# ProtoSnap-LilyPad_Development_Board.net
KiCad netlist of a schematic drawn in EAGLE
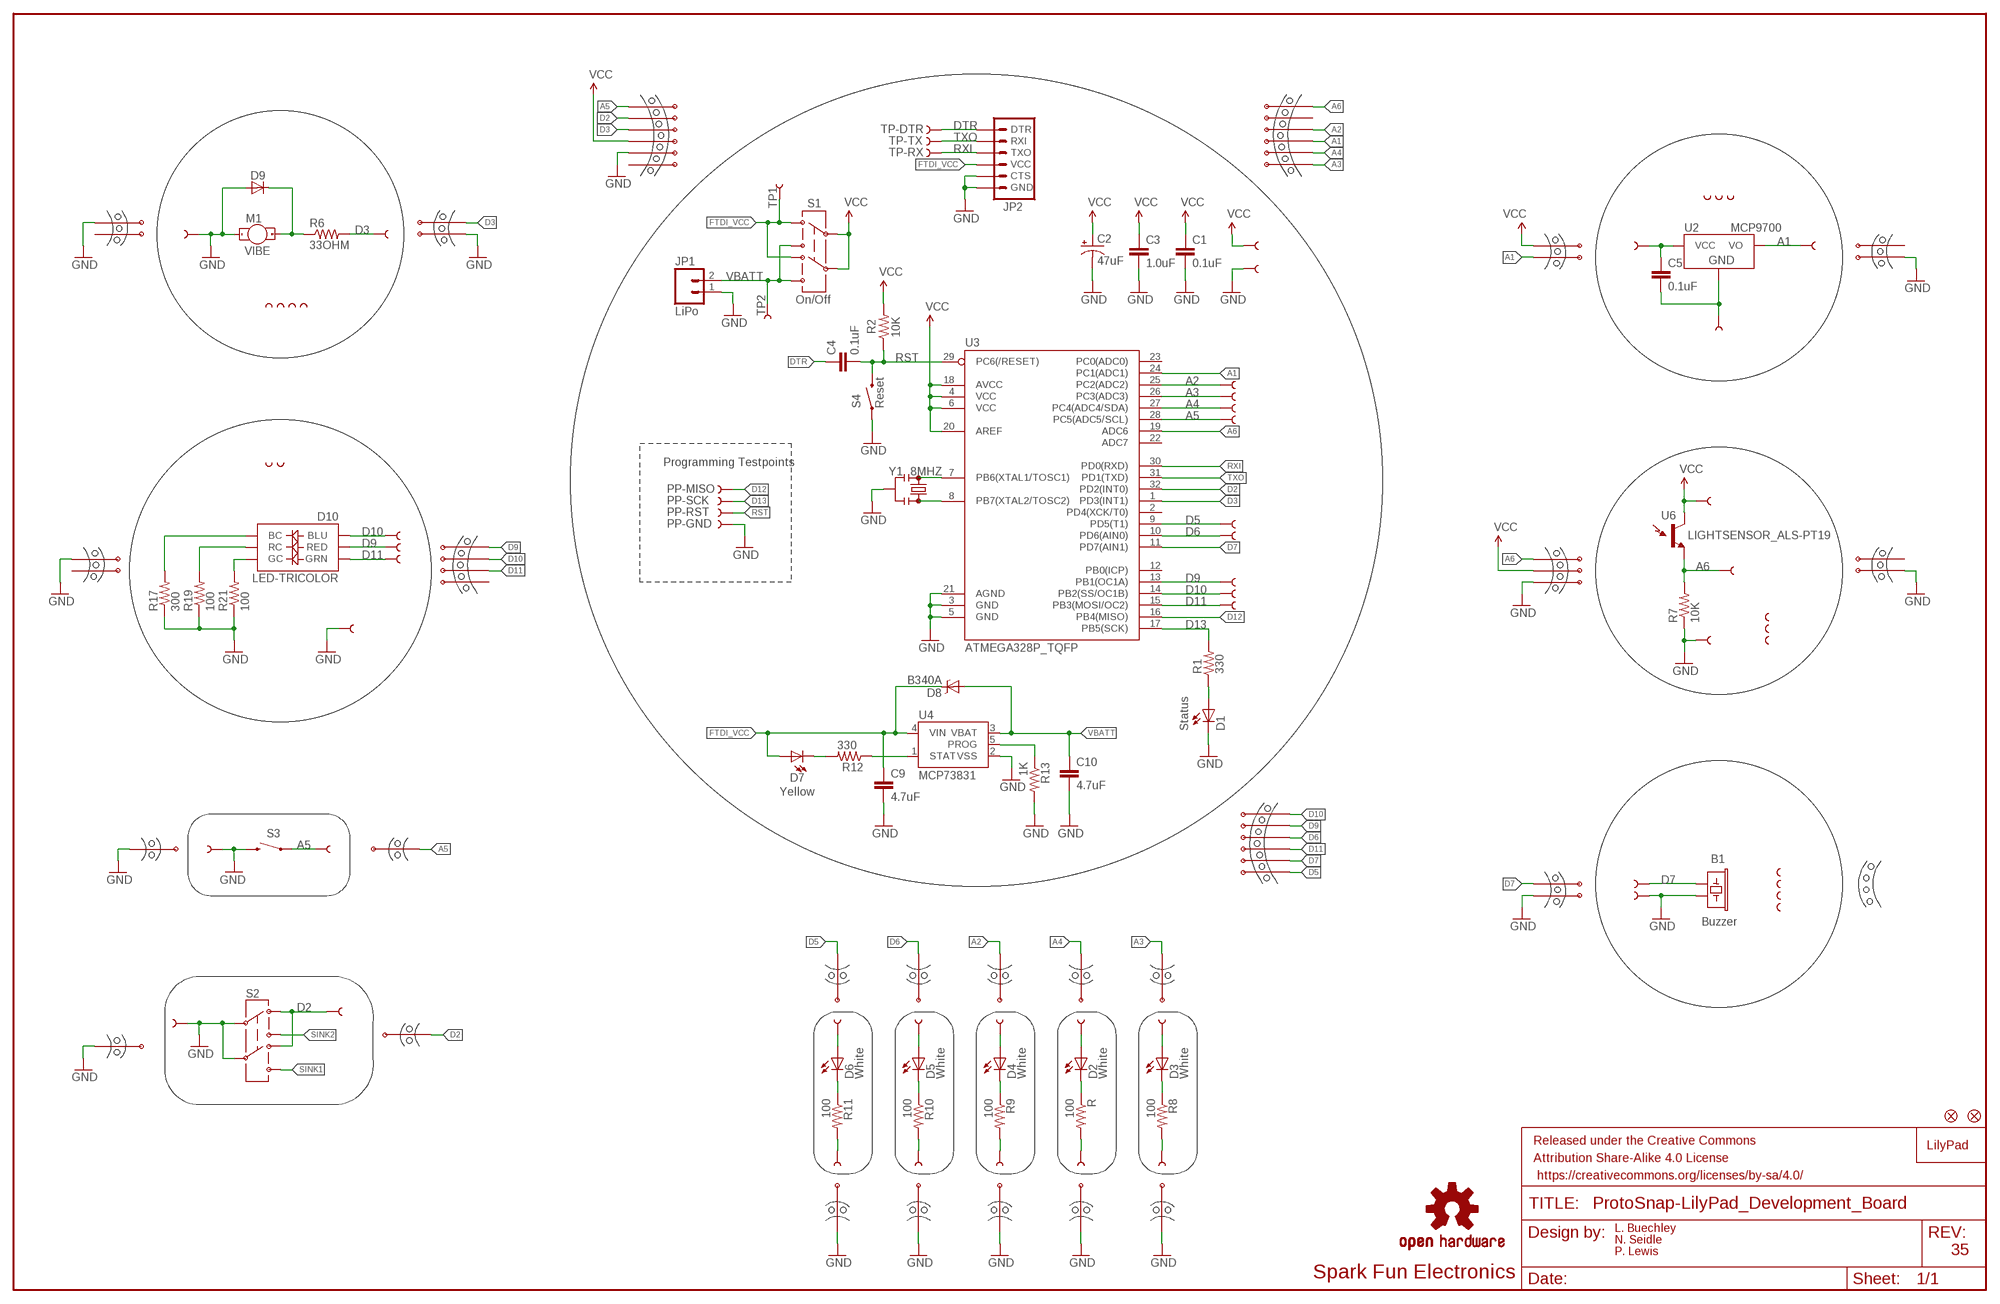
[diagram p0: schematic, sheet 1]

(export (version "E")
  (design (tool "Eeschema 10.0.6"))
  (components
    (comp (ref "1")
      (value "SEWTAP-NOHOLE2")
      (footprint "eagle-import:PETAL-NOHOLE-2SIDE")
      (libsource (lib "eagle-import") (part "SEWTAP-NOHOLE2"))
    )
    (comp (ref "2")
      (value "SEWTAP-NOHOLE2")
      (footprint "eagle-import:PETAL-NOHOLE-2SIDE")
      (libsource (lib "eagle-import") (part "SEWTAP-NOHOLE2"))
    )
    (comp (ref "3")
      (value "SEWTAP-NOHOLE2")
      (footprint "eagle-import:PETAL-NOHOLE-2SIDE")
      (libsource (lib "eagle-import") (part "SEWTAP-NOHOLE2"))
    )
    (comp (ref "4")
      (value "SEWTAP-NOHOLE2")
      (footprint "eagle-import:PETAL-NOHOLE-2SIDE")
      (libsource (lib "eagle-import") (part "SEWTAP-NOHOLE2"))
    )
    (comp (ref "A2/16")
      (value "SEWTAP9")
      (footprint "eagle-import:PETAL-LONG-1-2SIDE")
      (libsource (lib "eagle-import") (part "SEWTAP9"))
    )
    (comp (ref "A3/17")
      (value "SEWTAP9")
      (footprint "eagle-import:PETAL-LONG-1-2SIDE")
      (libsource (lib "eagle-import") (part "SEWTAP9"))
    )
    (comp (ref "A4/18")
      (value "SEWTAP9")
      (footprint "eagle-import:PETAL-LONG-1-2SIDE")
      (libsource (lib "eagle-import") (part "SEWTAP9"))
    )
    (comp (ref "A5/19")
      (value "SEWTAP9")
      (footprint "eagle-import:PETAL-LONG-1-2SIDE")
      (libsource (lib "eagle-import") (part "SEWTAP9"))
    )
    (comp (ref "B1")
      (value "Buzzer")
      (footprint "eagle-import:BUZZER-CCV")
      (libsource (lib "eagle-import") (part "BUZZERSMD2"))
    )
    (comp (ref "BUTTON-")
      (value "SEWTAP8")
      (footprint "eagle-import:PETAL-MEDIUM-2SIDE")
      (libsource (lib "eagle-import") (part "SEWTAP8"))
    )
    (comp (ref "BUTTONS")
      (value "SEWTAP8")
      (footprint "eagle-import:PETAL-MEDIUM-2SIDE")
      (libsource (lib "eagle-import") (part "SEWTAP8"))
    )
    (comp (ref "C1")
      (value "0.1uF")
      (footprint "eagle-import:0603-CAP")
      (libsource (lib "eagle-import") (part "0.1UF-25V(+80/-20%)(0603)"))
    )
    (comp (ref "C2")
      (value "47uF")
      (footprint "eagle-import:EIA3528")
      (libsource (lib "eagle-import") (part "47UF-10V-10%(TANT)"))
    )
    (comp (ref "C3")
      (value "1.0uF")
      (footprint "eagle-import:0603-CAP")
      (libsource (lib "eagle-import") (part "1.0UF-16V-10%(0603)"))
    )
    (comp (ref "C4")
      (value "0.1uF")
      (footprint "eagle-import:0603-CAP")
      (libsource (lib "eagle-import") (part "0.1UF-25V(+80/-20%)(0603)"))
    )
    (comp (ref "C5")
      (value "0.1uF")
      (footprint "eagle-import:0603-CAP")
      (libsource (lib "eagle-import") (part "CAP0603-CAP"))
    )
    (comp (ref "C9")
      (value "4.7uF")
      (footprint "eagle-import:0603-CAP")
      (libsource (lib "eagle-import") (part "4.7UF-6.3V-10%(0603)0603"))
    )
    (comp (ref "C10")
      (value "4.7uF")
      (footprint "eagle-import:0603-CAP")
      (libsource (lib "eagle-import") (part "4.7UF-6.3V-10%(0603)0603"))
    )
    (comp (ref "D1")
      (value "Status")
      (footprint "eagle-import:0603-LED-ALT1")
      (libsource (lib "eagle-import") (part "LEDLED-ALT1"))
    )
    (comp (ref "D2")
      (value "White")
      (footprint "eagle-import:LED-1206")
      (libsource (lib "eagle-import") (part "LED1206"))
    )
    (comp (ref "D3")
      (value "White")
      (footprint "eagle-import:LED-1206")
      (libsource (lib "eagle-import") (part "LED1206"))
    )
    (comp (ref "D4")
      (value "White")
      (footprint "eagle-import:LED-1206")
      (libsource (lib "eagle-import") (part "LED1206"))
    )
    (comp (ref "D5")
      (value "White")
      (footprint "eagle-import:LED-1206")
      (libsource (lib "eagle-import") (part "LED1206"))
    )
    (comp (ref "D6")
      (value "White")
      (footprint "eagle-import:LED-1206")
      (libsource (lib "eagle-import") (part "LED1206"))
    )
    (comp (ref "D7")
      (value "Yellow")
      (footprint "eagle-import:0603-LED-ALT1")
      (libsource (lib "eagle-import") (part "LEDLED-ALT1"))
    )
    (comp (ref "D8")
      (value "B340A")
      (footprint "eagle-import:SMA-DIODE")
      (libsource (lib "eagle-import") (part "DIODE-SCHOTTKY_"))
    )
    (comp (ref "D9")
      (value "DIODESOD")
      (footprint "eagle-import:SOD-323")
      (libsource (lib "eagle-import") (part "DIODESOD"))
    )
    (comp (ref "D10")
      (value "LED-TRICOLOR")
      (footprint "eagle-import:PLCC-6-LED")
      (libsource (lib "eagle-import") (part "LED-TRICOLOR-NO-COMPLCC-6-SMD"))
    )
    (comp (ref "FRAME1")
      (value "FRAME-LEDGER")
      (footprint "eagle-import:CREATIVE_COMMONS")
      (libsource (lib "eagle-import") (part "FRAME-LEDGER"))
    )
    (comp (ref "JP1")
      (value "LiPo")
      (footprint "eagle-import:JST-2-SMD")
      (libsource (lib "eagle-import") (part "M02-JST-2MM-SMT"))
    )
    (comp (ref "JP2")
      (value "ARDUINO_SERIAL_PROGRAMSMD")
      (footprint "eagle-import:1X06-SMD")
      (libsource (lib "eagle-import") (part "ARDUINO_SERIAL_PROGRAMSMD"))
    )
    (comp (ref "JP3")
      (value "FIDUCIAL1X2")
      (footprint "eagle-import:FIDUCIAL-1X2")
      (libsource (lib "eagle-import") (part "FIDUCIAL1X2"))
    )
    (comp (ref "JP4")
      (value "FIDUCIAL1X2")
      (footprint "eagle-import:FIDUCIAL-1X2")
      (libsource (lib "eagle-import") (part "FIDUCIAL1X2"))
    )
    (comp (ref "LED+")
      (value "SEWTAP6")
      (footprint "eagle-import:PETAL-SMALL-2SIDE")
      (libsource (lib "eagle-import") (part "SEWTAP6"))
    )
    (comp (ref "LED+1")
      (value "SEWTAP6")
      (footprint "eagle-import:PETAL-SMALL-2SIDE")
      (libsource (lib "eagle-import") (part "SEWTAP6"))
    )
    (comp (ref "LED+2")
      (value "SEWTAP6")
      (footprint "eagle-import:PETAL-SMALL-2SIDE")
      (libsource (lib "eagle-import") (part "SEWTAP6"))
    )
    (comp (ref "LED+3")
      (value "SEWTAP6")
      (footprint "eagle-import:PETAL-SMALL-2SIDE")
      (libsource (lib "eagle-import") (part "SEWTAP6"))
    )
    (comp (ref "LED+4")
      (value "SEWTAP6")
      (footprint "eagle-import:PETAL-SMALL-2SIDE")
      (libsource (lib "eagle-import") (part "SEWTAP6"))
    )
    (comp (ref "LED-")
      (value "SEWTAP6")
      (footprint "eagle-import:PETAL-SMALL-2SIDE")
      (libsource (lib "eagle-import") (part "SEWTAP6"))
    )
    (comp (ref "LED-1")
      (value "SEWTAP6")
      (footprint "eagle-import:PETAL-SMALL-2SIDE")
      (libsource (lib "eagle-import") (part "SEWTAP6"))
    )
    (comp (ref "LED-2")
      (value "SEWTAP6")
      (footprint "eagle-import:PETAL-SMALL-2SIDE")
      (libsource (lib "eagle-import") (part "SEWTAP6"))
    )
    (comp (ref "LED-3")
      (value "SEWTAP6")
      (footprint "eagle-import:PETAL-SMALL-2SIDE")
      (libsource (lib "eagle-import") (part "SEWTAP6"))
    )
    (comp (ref "LED-4")
      (value "SEWTAP6")
      (footprint "eagle-import:PETAL-SMALL-2SIDE")
      (libsource (lib "eagle-import") (part "SEWTAP6"))
    )
    (comp (ref "LIGHT+")
      (value "SEWTAP6")
      (footprint "eagle-import:PETAL-SMALL-2SIDE")
      (libsource (lib "eagle-import") (part "SEWTAP6"))
    )
    (comp (ref "LIGHT-")
      (value "SEWTAP6")
      (footprint "eagle-import:PETAL-SMALL-2SIDE")
      (libsource (lib "eagle-import") (part "SEWTAP6"))
    )
    (comp (ref "LIGHT1")
      (value "SEWTAP-NOHOLE2")
      (footprint "eagle-import:PETAL-NOHOLE-2SIDE")
      (libsource (lib "eagle-import") (part "SEWTAP-NOHOLE2"))
    )
    (comp (ref "LIGHT2")
      (value "SEWTAP-NOHOLE2")
      (footprint "eagle-import:PETAL-NOHOLE-2SIDE")
      (libsource (lib "eagle-import") (part "SEWTAP-NOHOLE2"))
    )
    (comp (ref "LIGHT3")
      (value "SEWTAP-NOHOLE2")
      (footprint "eagle-import:PETAL-NOHOLE-2SIDE")
      (libsource (lib "eagle-import") (part "SEWTAP-NOHOLE2"))
    )
    (comp (ref "LIGHTS")
      (value "SEWTAP6")
      (footprint "eagle-import:PETAL-SMALL-2SIDE")
      (libsource (lib "eagle-import") (part "SEWTAP6"))
    )
    (comp (ref "LOGO")
      (value "LOGO-LPLPA")
      (footprint "eagle-import:LOGO-LPA")
      (libsource (lib "eagle-import") (part "LOGO-LPLPA"))
    )
    (comp (ref "M1")
      (value "VIBE")
      (footprint "eagle-import:VIBE-MOTOR-10MM-SMD")
      (libsource (lib "eagle-import") (part "MOTORSMD"))
    )
    (comp (ref "PP-GND")
      (value "TEST-POINT3X5")
      (footprint "eagle-import:PAD.03X.05")
      (libsource (lib "eagle-import") (part "TEST-POINT3X5"))
    )
    (comp (ref "PP-MISO")
      (value "TEST-POINT3X5")
      (footprint "eagle-import:PAD.03X.05")
      (libsource (lib "eagle-import") (part "TEST-POINT3X5"))
    )
    (comp (ref "PP-RST")
      (value "TEST-POINT3X5")
      (footprint "eagle-import:PAD.03X.05")
      (libsource (lib "eagle-import") (part "TEST-POINT3X5"))
    )
    (comp (ref "PP-SCK")
      (value "TEST-POINT3X5")
      (footprint "eagle-import:PAD.03X.05")
      (libsource (lib "eagle-import") (part "TEST-POINT3X5"))
    )
    (comp (ref "R")
      (value "100")
      (footprint "eagle-import:0603-RES")
      (libsource (lib "eagle-import") (part "100OHM-1/10W-1%(0603)"))
    )
    (comp (ref "R1")
      (value "330")
      (footprint "eagle-import:0603-RES")
      (libsource (lib "eagle-import") (part "330OHM1/10W1%(0603)"))
    )
    (comp (ref "R2")
      (value "10K")
      (footprint "eagle-import:0603-RES")
      (libsource (lib "eagle-import") (part "10KOHM-1/10W-1%(0603)0603"))
    )
    (comp (ref "R6")
      (value "33OHM")
      (footprint "eagle-import:0603")
      (libsource (lib "eagle-import") (part "33OHM1/10W1%(0603)"))
    )
    (comp (ref "R7")
      (value "10K")
      (footprint "eagle-import:0603-RES")
      (libsource (lib "eagle-import") (part "10KOHM-1/10W-1%(0603)0603"))
    )
    (comp (ref "R8")
      (value "100")
      (footprint "eagle-import:0603-RES")
      (libsource (lib "eagle-import") (part "100OHM-1/10W-1%(0603)"))
    )
    (comp (ref "R9")
      (value "100")
      (footprint "eagle-import:0603-RES")
      (libsource (lib "eagle-import") (part "100OHM-1/10W-1%(0603)"))
    )
    (comp (ref "R10")
      (value "100")
      (footprint "eagle-import:0603-RES")
      (libsource (lib "eagle-import") (part "100OHM-1/10W-1%(0603)"))
    )
    (comp (ref "R11")
      (value "100")
      (footprint "eagle-import:0603-RES")
      (libsource (lib "eagle-import") (part "100OHM-1/10W-1%(0603)"))
    )
    (comp (ref "R12")
      (value "330")
      (footprint "eagle-import:0603-RES")
      (libsource (lib "eagle-import") (part "330OHM1/10W1%(0603)"))
    )
    (comp (ref "R13")
      (value "1K")
      (footprint "eagle-import:0603-RES")
      (libsource (lib "eagle-import") (part "1KOHM-1/10W-1%(0603)"))
    )
    (comp (ref "R17")
      (value "300")
      (footprint "eagle-import:0603-RES")
      (libsource (lib "eagle-import") (part "300OHM-1/10W-1%(0603)"))
    )
    (comp (ref "R19")
      (value "100")
      (footprint "eagle-import:0603-RES")
      (libsource (lib "eagle-import") (part "100OHM-1/10W-1%(0603)"))
    )
    (comp (ref "R21")
      (value "100")
      (footprint "eagle-import:0603-RES")
      (libsource (lib "eagle-import") (part "100OHM-1/10W-1%(0603)"))
    )
    (comp (ref "S1")
      (value "On/Off")
      (footprint "eagle-import:AYZ0202")
      (libsource (lib "eagle-import") (part "AYZ0202"))
    )
    (comp (ref "S2")
      (value "AYZ0202")
      (footprint "eagle-import:AYZ0202")
      (libsource (lib "eagle-import") (part "AYZ0202"))
    )
    (comp (ref "S3")
      (value "SWITCH-MOMENTARY-2SMD-REDUNDANT")
      (footprint "eagle-import:TACTILE-SWITCH-SMD")
      (libsource (lib "eagle-import") (part "SWITCH-MOMENTARY-2SMD-REDUNDANT"))
    )
    (comp (ref "S4")
      (value "Reset")
      (footprint "eagle-import:TACTILE-SWITCH-SMD")
      (libsource (lib "eagle-import") (part "SWITCH-MOMENTARY-2SMD-REDUNDANT"))
    )
    (comp (ref "SLIDEOFF")
      (value "SEWTAP8")
      (footprint "eagle-import:PETAL-MEDIUM-2SIDE")
      (libsource (lib "eagle-import") (part "SEWTAP8"))
    )
    (comp (ref "SLIDEON")
      (value "SEWTAP8")
      (footprint "eagle-import:PETAL-MEDIUM-2SIDE")
      (libsource (lib "eagle-import") (part "SEWTAP8"))
    )
    (comp (ref "TEMP+")
      (value "SEWTAP6")
      (footprint "eagle-import:PETAL-SMALL-2SIDE")
      (libsource (lib "eagle-import") (part "SEWTAP6"))
    )
    (comp (ref "TEMP-")
      (value "SEWTAP6")
      (footprint "eagle-import:PETAL-SMALL-2SIDE")
      (libsource (lib "eagle-import") (part "SEWTAP6"))
    )
    (comp (ref "TEMP1")
      (value "SEWTAP-NOHOLE2")
      (footprint "eagle-import:PETAL-NOHOLE-2SIDE")
      (libsource (lib "eagle-import") (part "SEWTAP-NOHOLE2"))
    )
    (comp (ref "TEMP2")
      (value "SEWTAP-NOHOLE2")
      (footprint "eagle-import:PETAL-NOHOLE-2SIDE")
      (libsource (lib "eagle-import") (part "SEWTAP-NOHOLE2"))
    )
    (comp (ref "TEMP3")
      (value "SEWTAP-NOHOLE2")
      (footprint "eagle-import:PETAL-NOHOLE-2SIDE")
      (libsource (lib "eagle-import") (part "SEWTAP-NOHOLE2"))
    )
    (comp (ref "TEMPS")
      (value "SEWTAP6")
      (footprint "eagle-import:PETAL-SMALL-2SIDE")
      (libsource (lib "eagle-import") (part "SEWTAP6"))
    )
    (comp (ref "TP-DTR")
      (value "TEST-POINT3X5")
      (footprint "eagle-import:PAD.03X.05")
      (libsource (lib "eagle-import") (part "TEST-POINT3X5"))
    )
    (comp (ref "TP-RX")
      (value "TEST-POINT3X5")
      (footprint "eagle-import:PAD.03X.05")
      (libsource (lib "eagle-import") (part "TEST-POINT3X5"))
    )
    (comp (ref "TP-TX")
      (value "TEST-POINT3X5")
      (footprint "eagle-import:PAD.03X.05")
      (libsource (lib "eagle-import") (part "TEST-POINT3X5"))
    )
    (comp (ref "TP1")
      (value "TEST-POINT3X5")
      (footprint "eagle-import:PAD.03X.05")
      (libsource (lib "eagle-import") (part "TEST-POINT3X5"))
    )
    (comp (ref "TP2")
      (value "TEST-POINT3X5")
      (footprint "eagle-import:PAD.03X.05")
      (libsource (lib "eagle-import") (part "TEST-POINT3X5"))
    )
    (comp (ref "U$1")
      (value "SEWTAP9")
      (footprint "eagle-import:PETAL-LONG-1-2SIDE")
      (libsource (lib "eagle-import") (part "SEWTAP9"))
    )
    (comp (ref "U$2")
      (value "MOUSE-BITE-2")
      (footprint "eagle-import:MOUSE-BITE-2")
      (libsource (lib "eagle-import") (part "MOUSE-BITE-2"))
    )
    (comp (ref "U$3")
      (value "MOUSE-BITE-2")
      (footprint "eagle-import:MOUSE-BITE-2")
      (libsource (lib "eagle-import") (part "MOUSE-BITE-2"))
    )
    (comp (ref "U$4")
      (value "SEWTAP9")
      (footprint "eagle-import:PETAL-LONG-1-2SIDE")
      (libsource (lib "eagle-import") (part "SEWTAP9"))
    )
    (comp (ref "U$5")
      (value "MOUSE-BITE-2")
      (footprint "eagle-import:MOUSE-BITE-2")
      (libsource (lib "eagle-import") (part "MOUSE-BITE-2"))
    )
    (comp (ref "U$6")
      (value "MOUSE-BITE-2")
      (footprint "eagle-import:MOUSE-BITE-2")
      (libsource (lib "eagle-import") (part "MOUSE-BITE-2"))
    )
    (comp (ref "U$7")
      (value "MOUSE-BITE-66")
      (footprint "eagle-import:MOUSE-BITE-6")
      (libsource (lib "eagle-import") (part "MOUSE-BITE-66"))
    )
    (comp (ref "U$8")
      (value "MOUSE-BITE-66")
      (footprint "eagle-import:MOUSE-BITE-6")
      (libsource (lib "eagle-import") (part "MOUSE-BITE-66"))
    )
    (comp (ref "U$10")
      (value "MOUSE-BITE-12_HOLES")
      (footprint "eagle-import:MOUST-BITE-1-(2_HOLES)")
      (libsource (lib "eagle-import") (part "MOUSE-BITE-12_HOLES"))
    )
    (comp (ref "U$11")
      (value "MOUSE-BITE-12_HOLES")
      (footprint "eagle-import:MOUST-BITE-1-(2_HOLES)")
      (libsource (lib "eagle-import") (part "MOUSE-BITE-12_HOLES"))
    )
    (comp (ref "U$12")
      (value "MOUSE-BITE-12_HOLES")
      (footprint "eagle-import:MOUST-BITE-1-(2_HOLES)")
      (libsource (lib "eagle-import") (part "MOUSE-BITE-12_HOLES"))
    )
    (comp (ref "U$13")
      (value "MOUSE-BITE-12_HOLES")
      (footprint "eagle-import:MOUST-BITE-1-(2_HOLES)")
      (libsource (lib "eagle-import") (part "MOUSE-BITE-12_HOLES"))
    )
    (comp (ref "U$14")
      (value "MOUSE-BITE-12_HOLES")
      (footprint "eagle-import:MOUST-BITE-1-(2_HOLES)")
      (libsource (lib "eagle-import") (part "MOUSE-BITE-12_HOLES"))
    )
    (comp (ref "U$15")
      (value "MOUSE-BITE-12_HOLES")
      (footprint "eagle-import:MOUST-BITE-1-(2_HOLES)")
      (libsource (lib "eagle-import") (part "MOUSE-BITE-12_HOLES"))
    )
    (comp (ref "U$16")
      (value "MOUSE-BITE-12_HOLES")
      (footprint "eagle-import:MOUST-BITE-1-(2_HOLES)")
      (libsource (lib "eagle-import") (part "MOUSE-BITE-12_HOLES"))
    )
    (comp (ref "U$17")
      (value "MOUSE-BITE-12_HOLES")
      (footprint "eagle-import:MOUST-BITE-1-(2_HOLES)")
      (libsource (lib "eagle-import") (part "MOUSE-BITE-12_HOLES"))
    )
    (comp (ref "U$18")
      (value "MOUSE-BITE-12_HOLES")
      (footprint "eagle-import:MOUST-BITE-1-(2_HOLES)")
      (libsource (lib "eagle-import") (part "MOUSE-BITE-12_HOLES"))
    )
    (comp (ref "U$19")
      (value "MOUSE-BITE-12_HOLES")
      (footprint "eagle-import:MOUST-BITE-1-(2_HOLES)")
      (libsource (lib "eagle-import") (part "MOUSE-BITE-12_HOLES"))
    )
    (comp (ref "U$20")
      (value "MOUSE-BITE-4")
      (footprint "eagle-import:MOUSE-BITE-4")
      (libsource (lib "eagle-import") (part "MOUSE-BITE-4"))
    )
    (comp (ref "U$22")
      (value "SEWTAP6")
      (footprint "eagle-import:PETAL-SMALL-2SIDE")
      (libsource (lib "eagle-import") (part "SEWTAP6"))
    )
    (comp (ref "U$23")
      (value "SEWTAP6")
      (footprint "eagle-import:PETAL-SMALL-2SIDE")
      (libsource (lib "eagle-import") (part "SEWTAP6"))
    )
    (comp (ref "U$24")
      (value "SEWTAP6")
      (footprint "eagle-import:PETAL-SMALL-2SIDE")
      (libsource (lib "eagle-import") (part "SEWTAP6"))
    )
    (comp (ref "U$25")
      (value "SEWTAP6")
      (footprint "eagle-import:PETAL-SMALL-2SIDE")
      (libsource (lib "eagle-import") (part "SEWTAP6"))
    )
    (comp (ref "U$26")
      (value "SEWTAP-NOHOLE2")
      (footprint "eagle-import:PETAL-NOHOLE-2SIDE")
      (libsource (lib "eagle-import") (part "SEWTAP-NOHOLE2"))
    )
    (comp (ref "U$27")
      (value "SEWTAP-NOHOLE2")
      (footprint "eagle-import:PETAL-NOHOLE-2SIDE")
      (libsource (lib "eagle-import") (part "SEWTAP-NOHOLE2"))
    )
    (comp (ref "U$32")
      (value "MOUSE-BITE-2")
      (footprint "eagle-import:MOUSE-BITE-2")
      (libsource (lib "eagle-import") (part "MOUSE-BITE-2"))
    )
    (comp (ref "U$32-")
      (value "SEWTAP6")
      (footprint "eagle-import:PETAL-SMALL-2SIDE")
      (libsource (lib "eagle-import") (part "SEWTAP6"))
    )
    (comp (ref "U$33")
      (value "MOUSE-BITE-3")
      (footprint "eagle-import:MOUSE-BITE-3")
      (libsource (lib "eagle-import") (part "MOUSE-BITE-3"))
    )
    (comp (ref "U$33+")
      (value "SEWTAP6")
      (footprint "eagle-import:PETAL-SMALL-2SIDE")
      (libsource (lib "eagle-import") (part "SEWTAP6"))
    )
    (comp (ref "U$37")
      (value "SEWTAP9")
      (footprint "eagle-import:PETAL-LONG-1-2SIDE")
      (libsource (lib "eagle-import") (part "SEWTAP9"))
    )
    (comp (ref "U$39")
      (value "SEWTAP9")
      (footprint "eagle-import:PETAL-LONG-1-2SIDE")
      (libsource (lib "eagle-import") (part "SEWTAP9"))
    )
    (comp (ref "U$40")
      (value "MOUSE-BITE-12_HOLES")
      (footprint "eagle-import:MOUST-BITE-1-(2_HOLES)")
      (libsource (lib "eagle-import") (part "MOUSE-BITE-12_HOLES"))
    )
    (comp (ref "U$41")
      (value "SEWTAP9")
      (footprint "eagle-import:PETAL-LONG-1-2SIDE")
      (libsource (lib "eagle-import") (part "SEWTAP9"))
    )
    (comp (ref "U$42")
      (value "MOUSE-BITE-12_HOLES")
      (footprint "eagle-import:MOUST-BITE-1-(2_HOLES)")
      (libsource (lib "eagle-import") (part "MOUSE-BITE-12_HOLES"))
    )
    (comp (ref "U$43")
      (value "SEWTAP9")
      (footprint "eagle-import:PETAL-LONG-1-2SIDE")
      (libsource (lib "eagle-import") (part "SEWTAP9"))
    )
    (comp (ref "U$44")
      (value "MOUSE-BITE-12_HOLES")
      (footprint "eagle-import:MOUST-BITE-1-(2_HOLES)")
      (libsource (lib "eagle-import") (part "MOUSE-BITE-12_HOLES"))
    )
    (comp (ref "U$45")
      (value "SEWTAP9")
      (footprint "eagle-import:PETAL-LONG-1-2SIDE")
      (libsource (lib "eagle-import") (part "SEWTAP9"))
    )
    (comp (ref "U$46")
      (value "MOUSE-BITE-12_HOLES")
      (footprint "eagle-import:MOUST-BITE-1-(2_HOLES)")
      (libsource (lib "eagle-import") (part "MOUSE-BITE-12_HOLES"))
    )
    (comp (ref "U$47")
      (value "MOUSE-BITE-2")
      (footprint "eagle-import:MOUSE-BITE-2")
      (libsource (lib "eagle-import") (part "MOUSE-BITE-2"))
    )
    (comp (ref "U$48")
      (value "MOUSE-BITE-2")
      (footprint "eagle-import:MOUSE-BITE-2")
      (libsource (lib "eagle-import") (part "MOUSE-BITE-2"))
    )
    (comp (ref "U$49")
      (value "MOUSE-BITE-3(NO_PADS)")
      (footprint "eagle-import:MOUSE-BITE-3(NO_PADS)")
      (libsource (lib "eagle-import") (part "MOUSE-BITE-3(NO_PADS)"))
    )
    (comp (ref "U$51")
      (value "MOUSE-BITE-66")
      (footprint "eagle-import:MOUSE-BITE-6")
      (libsource (lib "eagle-import") (part "MOUSE-BITE-66"))
    )
    (comp (ref "U$52")
      (value "OSHW-LOGOS")
      (footprint "eagle-import:OSHW-LOGO-S")
      (libsource (lib "eagle-import") (part "OSHW-LOGOS"))
    )
    (comp (ref "U2")
      (value "MCP9700")
      (footprint "eagle-import:SOT23-3")
      (libsource (lib "eagle-import") (part "MCP9700SMD"))
    )
    (comp (ref "U3")
      (value "ATMEGA328P_TQFP")
      (footprint "eagle-import:TQFP32-08")
      (libsource (lib "eagle-import") (part "ATMEGA328P_TQFP"))
    )
    (comp (ref "U4")
      (value "MCP73831")
      (footprint "eagle-import:SOT23-5")
      (libsource (lib "eagle-import") (part "MCP73831"))
    )
    (comp (ref "U6")
      (value "LIGHTSENSOR_ALS-PT19")
      (footprint "eagle-import:ALS-PT19")
      (libsource (lib "eagle-import") (part "LIGHTSENSORALS"))
    )
    (comp (ref "VIBE+")
      (value "SEWTAP6")
      (footprint "eagle-import:PETAL-SMALL-2SIDE")
      (libsource (lib "eagle-import") (part "SEWTAP6"))
    )
    (comp (ref "VIBE-")
      (value "SEWTAP6")
      (footprint "eagle-import:PETAL-SMALL-2SIDE")
      (libsource (lib "eagle-import") (part "SEWTAP6"))
    )
    (comp (ref "VIBE1")
      (value "SEWTAP-NOHOLE2")
      (footprint "eagle-import:PETAL-NOHOLE-2SIDE")
      (libsource (lib "eagle-import") (part "SEWTAP-NOHOLE2"))
    )
    (comp (ref "VIBE2")
      (value "SEWTAP-NOHOLE2")
      (footprint "eagle-import:PETAL-NOHOLE-2SIDE")
      (libsource (lib "eagle-import") (part "SEWTAP-NOHOLE2"))
    )
    (comp (ref "VIBE3")
      (value "SEWTAP-NOHOLE2")
      (footprint "eagle-import:PETAL-NOHOLE-2SIDE")
      (libsource (lib "eagle-import") (part "SEWTAP-NOHOLE2"))
    )
    (comp (ref "VIBE4")
      (value "SEWTAP-NOHOLE2")
      (footprint "eagle-import:PETAL-NOHOLE-2SIDE")
      (libsource (lib "eagle-import") (part "SEWTAP-NOHOLE2"))
    )
    (comp (ref "Y1")
      (value "8MHZ")
      (footprint "eagle-import:RESONATOR-SMD")
      (libsource (lib "eagle-import") (part "RESONATOR8MHZ"))
    )
  )
  (nets
    (net (code "1") (name "A1") (class "Default")
      (node (ref "TEMPS") (pin "1") (pinfunction "1_1") (pintype "bidirectional"))
      (node (ref "U$2") (pin "P$1") (pinfunction "P$1_P$1") (pintype "bidirectional"))
      (node (ref "U$7") (pin "P$4") (pinfunction "P$4_P$4") (pintype "bidirectional"))
      (node (ref "U2") (pin "2") (pinfunction "VO_2") (pintype "bidirectional"))
      (node (ref "U3") (pin "24") (pinfunction "PC1(ADC1)_24") (pintype "bidirectional"))
    )
    (net (code "2") (name "A2") (class "Default")
      (node (ref "A2/16") (pin "1") (pinfunction "1_1") (pintype "bidirectional"))
      (node (ref "U$12") (pin "P$1") (pinfunction "P$1_P$1") (pintype "bidirectional"))
      (node (ref "U$7") (pin "P$3") (pinfunction "P$3_P$3") (pintype "bidirectional"))
      (node (ref "U3") (pin "25") (pinfunction "PC2(ADC2)_25") (pintype "bidirectional"))
    )
    (net (code "3") (name "A3") (class "Default")
      (node (ref "A3/17") (pin "1") (pinfunction "1_1") (pintype "bidirectional"))
      (node (ref "U$13") (pin "P$1") (pinfunction "P$1_P$1") (pintype "bidirectional"))
      (node (ref "U$7") (pin "P$6") (pinfunction "P$6_P$6") (pintype "bidirectional"))
      (node (ref "U3") (pin "26") (pinfunction "PC3(ADC3)_26") (pintype "bidirectional"))
    )
    (net (code "4") (name "A4") (class "Default")
      (node (ref "A4/18") (pin "1") (pinfunction "1_1") (pintype "bidirectional"))
      (node (ref "U$14") (pin "P$1") (pinfunction "P$1_P$1") (pintype "bidirectional"))
      (node (ref "U$7") (pin "P$5") (pinfunction "P$5_P$5") (pintype "bidirectional"))
      (node (ref "U3") (pin "27") (pinfunction "PC4(ADC4/SDA)_27") (pintype "bidirectional"))
    )
    (net (code "5") (name "A5") (class "Default")
      (node (ref "A5/19") (pin "1") (pinfunction "1_1") (pintype "bidirectional"))
      (node (ref "BUTTONS") (pin "1") (pinfunction "1_1") (pintype "bidirectional"))
      (node (ref "S3") (pin "1") (pinfunction "1_1") (pintype "passive"))
      (node (ref "S3") (pin "2") (pinfunction "1_2") (pintype "passive"))
      (node (ref "U$40") (pin "P$1") (pinfunction "P$1_P$1") (pintype "bidirectional"))
      (node (ref "U$8") (pin "P$1") (pinfunction "P$1_P$1") (pintype "bidirectional"))
      (node (ref "U3") (pin "28") (pinfunction "PC5(ADC5/SCL)_28") (pintype "bidirectional"))
    )
    (net (code "6") (name "A6") (class "Default")
      (node (ref "LIGHTS") (pin "1") (pinfunction "1_1") (pintype "bidirectional"))
      (node (ref "R7") (pin "2") (pinfunction "2_2") (pintype "passive"))
      (node (ref "U$33") (pin "P$1") (pinfunction "P$1_P$1") (pintype "bidirectional"))
      (node (ref "U$7") (pin "P$1") (pinfunction "P$1_P$1") (pintype "bidirectional"))
      (node (ref "U3") (pin "19") (pinfunction "ADC6_19") (pintype "bidirectional"))
      (node (ref "U6") (pin "E") (pinfunction "E1_E") (pintype "passive"))
    )
    (net (code "7") (name "D2") (class "Default")
      (node (ref "S2") (pin "3") (pinfunction "1_3") (pintype "bidirectional"))
      (node (ref "S2") (pin "6") (pinfunction "4_6") (pintype "bidirectional"))
      (node (ref "SLIDEON") (pin "1") (pinfunction "1_1") (pintype "bidirectional"))
      (node (ref "U$46") (pin "P$1") (pinfunction "P$1_P$1") (pintype "bidirectional"))
      (node (ref "U$8") (pin "P$2") (pinfunction "P$2_P$2") (pintype "bidirectional"))
      (node (ref "U3") (pin "32") (pinfunction "PD2(INT0)_32") (pintype "bidirectional"))
    )
    (net (code "8") (name "D3") (class "Default")
      (node (ref "R6") (pin "2") (pinfunction "2_2") (pintype "passive"))
      (node (ref "U$5") (pin "P$1") (pinfunction "P$1_P$1") (pintype "bidirectional"))
      (node (ref "U$8") (pin "P$3") (pinfunction "P$3_P$3") (pintype "bidirectional"))
      (node (ref "U3") (pin "1") (pinfunction "PD3(INT1)_1") (pintype "bidirectional"))
      (node (ref "VIBE+") (pin "1") (pinfunction "1_1") (pintype "bidirectional"))
    )
    (net (code "9") (name "D5") (class "Default")
      (node (ref "U$10") (pin "P$1") (pinfunction "P$1_P$1") (pintype "bidirectional"))
      (node (ref "U$41") (pin "1") (pinfunction "1_1") (pintype "bidirectional"))
      (node (ref "U$51") (pin "P$1") (pinfunction "P$1_P$1") (pintype "bidirectional"))
      (node (ref "U3") (pin "9") (pinfunction "PD5(T1)_9") (pintype "bidirectional"))
    )
    (net (code "10") (name "D6") (class "Default")
      (node (ref "U$1") (pin "1") (pinfunction "1_1") (pintype "bidirectional"))
      (node (ref "U$11") (pin "P$1") (pinfunction "P$1_P$1") (pintype "bidirectional"))
      (node (ref "U$51") (pin "P$4") (pinfunction "P$4_P$4") (pintype "bidirectional"))
      (node (ref "U3") (pin "10") (pinfunction "PD6(AIN0)_10") (pintype "bidirectional"))
    )
    (net (code "11") (name "D7") (class "Default")
      (node (ref "B1") (pin "+") (pinfunction "1_+") (pintype "passive"))
      (node (ref "U$32") (pin "P$2") (pinfunction "P$2_P$2") (pintype "bidirectional"))
      (node (ref "U$33+") (pin "1") (pinfunction "1_1") (pintype "bidirectional"))
      (node (ref "U$51") (pin "P$2") (pinfunction "P$2_P$2") (pintype "bidirectional"))
      (node (ref "U3") (pin "11") (pinfunction "PD7(AIN1)_11") (pintype "bidirectional"))
    )
    (net (code "12") (name "D9") (class "Default")
      (node (ref "D10") (pin "AR") (pinfunction "RED_AR") (pintype "bidirectional"))
      (node (ref "U$20") (pin "P$4") (pinfunction "P$4_P$4") (pintype "bidirectional"))
      (node (ref "U$22") (pin "1") (pinfunction "1_1") (pintype "bidirectional"))
      (node (ref "U$37") (pin "1") (pinfunction "1_1") (pintype "bidirectional"))
      (node (ref "U$51") (pin "P$5") (pinfunction "P$5_P$5") (pintype "bidirectional"))
      (node (ref "U3") (pin "13") (pinfunction "PB1(OC1A)_13") (pintype "bidirectional"))
    )
    (net (code "13") (name "D10") (class "Default")
      (node (ref "D10") (pin "AB") (pinfunction "BLU_AB") (pintype "bidirectional"))
      (node (ref "U$20") (pin "P$3") (pinfunction "P$3_P$3") (pintype "bidirectional"))
      (node (ref "U$24") (pin "1") (pinfunction "1_1") (pintype "bidirectional"))
      (node (ref "U$39") (pin "1") (pinfunction "1_1") (pintype "bidirectional"))
      (node (ref "U$51") (pin "P$6") (pinfunction "P$6_P$6") (pintype "bidirectional"))
      (node (ref "U3") (pin "14") (pinfunction "PB2(SS/OC1B)_14") (pintype "bidirectional"))
    )
    (net (code "14") (name "D11") (class "Default")
      (node (ref "D10") (pin "AG") (pinfunction "GRN_AG") (pintype "bidirectional"))
      (node (ref "U$20") (pin "P$2") (pinfunction "P$2_P$2") (pintype "bidirectional"))
      (node (ref "U$23") (pin "1") (pinfunction "1_1") (pintype "bidirectional"))
      (node (ref "U$4") (pin "1") (pinfunction "1_1") (pintype "bidirectional"))
      (node (ref "U$51") (pin "P$3") (pinfunction "P$3_P$3") (pintype "bidirectional"))
      (node (ref "U3") (pin "15") (pinfunction "PB3(MOSI/OC2)_15") (pintype "bidirectional"))
    )
    (net (code "15") (name "D12") (class "Default")
      (node (ref "PP-MISO") (pin "P$1") (pinfunction "1_P$1") (pintype "bidirectional"))
      (node (ref "U3") (pin "16") (pinfunction "PB4(MISO)_16") (pintype "bidirectional"))
    )
    (net (code "16") (name "D13") (class "Default")
      (node (ref "PP-SCK") (pin "P$1") (pinfunction "1_P$1") (pintype "bidirectional"))
      (node (ref "R1") (pin "2") (pinfunction "2_2") (pintype "passive"))
      (node (ref "U3") (pin "17") (pinfunction "PB5(SCK)_17") (pintype "bidirectional"))
    )
    (net (code "17") (name "DTR") (class "Default")
      (node (ref "C4") (pin "1") (pinfunction "1_1") (pintype "passive"))
      (node (ref "JP2") (pin "1") (pinfunction "DTR_1") (pintype "passive"))
      (node (ref "TP-DTR") (pin "P$1") (pinfunction "1_P$1") (pintype "bidirectional"))
    )
    (net (code "18") (name "FTDI_VCC") (class "Default")
      (node (ref "C9") (pin "1") (pinfunction "1_1") (pintype "passive"))
      (node (ref "D7") (pin "A") (pinfunction "A_A") (pintype "passive"))
      (node (ref "D8") (pin "C") (pinfunction "C_C") (pintype "passive"))
      (node (ref "JP2") (pin "4") (pinfunction "VCC_4") (pintype "passive"))
      (node (ref "S1") (pin "3") (pinfunction "1_3") (pintype "bidirectional"))
      (node (ref "S1") (pin "6") (pinfunction "4_6") (pintype "bidirectional"))
      (node (ref "TP1") (pin "P$1") (pinfunction "1_P$1") (pintype "bidirectional"))
      (node (ref "U4") (pin "4") (pinfunction "VIN_4") (pintype "power_in"))
    )
    (net (code "19") (name "GND") (class "Default")
      (node (ref "B1") (pin "-") (pinfunction "2_-") (pintype "passive"))
      (node (ref "BUTTON-") (pin "1") (pinfunction "1_1") (pintype "bidirectional"))
      (node (ref "C1") (pin "2") (pinfunction "2_2") (pintype "passive"))
      (node (ref "C10") (pin "2") (pinfunction "2_2") (pintype "passive"))
      (node (ref "C2") (pin "C") (pinfunction "-_C") (pintype "passive"))
      (node (ref "C3") (pin "2") (pinfunction "2_2") (pintype "passive"))
      (node (ref "C5") (pin "2") (pinfunction "2_2") (pintype "passive"))
      (node (ref "C9") (pin "2") (pinfunction "2_2") (pintype "passive"))
      (node (ref "D1") (pin "C") (pinfunction "C_C") (pintype "passive"))
      (node (ref "D9") (pin "2") (pinfunction "A_2") (pintype "passive"))
      (node (ref "JP1") (pin "1") (pinfunction "1_1") (pintype "passive"))
      (node (ref "JP2") (pin "5") (pinfunction "CTS_5") (pintype "passive"))
      (node (ref "JP2") (pin "6") (pinfunction "GND_6") (pintype "passive"))
      (node (ref "LIGHT-") (pin "1") (pinfunction "1_1") (pintype "bidirectional"))
      (node (ref "M1") (pin "P$2") (pinfunction "-_P$2") (pintype "bidirectional"))
      (node (ref "PP-GND") (pin "P$1") (pinfunction "1_P$1") (pintype "bidirectional"))
      (node (ref "R13") (pin "2") (pinfunction "2_2") (pintype "passive"))
      (node (ref "R17") (pin "1") (pinfunction "1_1") (pintype "passive"))
      (node (ref "R19") (pin "1") (pinfunction "1_1") (pintype "passive"))
      (node (ref "R21") (pin "1") (pinfunction "1_1") (pintype "passive"))
      (node (ref "R7") (pin "1") (pinfunction "1_1") (pintype "passive"))
      (node (ref "S2") (pin "2") (pinfunction "2_2") (pintype "bidirectional"))
      (node (ref "S2") (pin "5") (pinfunction "5_5") (pintype "bidirectional"))
      (node (ref "S3") (pin "3") (pinfunction "2_3") (pintype "passive"))
      (node (ref "S3") (pin "4") (pinfunction "2_4") (pintype "passive"))
      (node (ref "S4") (pin "1") (pinfunction "1_1") (pintype "passive"))
      (node (ref "S4") (pin "2") (pinfunction "1_2") (pintype "passive"))
      (node (ref "SLIDEOFF") (pin "1") (pinfunction "1_1") (pintype "bidirectional"))
      (node (ref "TEMP-") (pin "1") (pinfunction "1_1") (pintype "bidirectional"))
      (node (ref "U$15") (pin "P$1") (pinfunction "P$1_P$1") (pintype "bidirectional"))
      (node (ref "U$16") (pin "P$1") (pinfunction "P$1_P$1") (pintype "bidirectional"))
      (node (ref "U$17") (pin "P$1") (pinfunction "P$1_P$1") (pintype "bidirectional"))
      (node (ref "U$18") (pin "P$1") (pinfunction "P$1_P$1") (pintype "bidirectional"))
      (node (ref "U$19") (pin "P$1") (pinfunction "P$1_P$1") (pintype "bidirectional"))
      (node (ref "U$25") (pin "1") (pinfunction "1_1") (pintype "bidirectional"))
      (node (ref "U$3") (pin "P$1") (pinfunction "P$1_P$1") (pintype "bidirectional"))
      (node (ref "U$32") (pin "P$1") (pinfunction "P$1_P$1") (pintype "bidirectional"))
      (node (ref "U$32-") (pin "1") (pinfunction "1_1") (pintype "bidirectional"))
      (node (ref "U$33") (pin "P$3") (pinfunction "P$3_P$3") (pintype "bidirectional"))
      (node (ref "U$42") (pin "P$1") (pinfunction "P$1_P$1") (pintype "bidirectional"))
      (node (ref "U$43") (pin "1") (pinfunction "1_1") (pintype "bidirectional"))
      (node (ref "U$44") (pin "P$1") (pinfunction "P$1_P$1") (pintype "bidirectional"))
      (node (ref "U$47") (pin "P$1") (pinfunction "P$1_P$1") (pintype "bidirectional"))
      (node (ref "U$48") (pin "P$1") (pinfunction "P$1_P$1") (pintype "bidirectional"))
      (node (ref "U$5") (pin "P$2") (pinfunction "P$2_P$2") (pintype "bidirectional"))
      (node (ref "U$6") (pin "P$1") (pinfunction "P$1_P$1") (pintype "bidirectional"))
      (node (ref "U$8") (pin "P$5") (pinfunction "P$5_P$5") (pintype "bidirectional"))
      (node (ref "U2") (pin "3") (pinfunction "GND_3") (pintype "bidirectional"))
      (node (ref "U3") (pin "21") (pinfunction "AGND_21") (pintype "bidirectional"))
      (node (ref "U3") (pin "3") (pinfunction "GND_3") (pintype "bidirectional"))
      (node (ref "U3") (pin "5") (pinfunction "GND_5") (pintype "bidirectional"))
      (node (ref "U4") (pin "2") (pinfunction "VSS_2") (pintype "power_in"))
      (node (ref "VIBE-") (pin "1") (pinfunction "1_1") (pintype "bidirectional"))
      (node (ref "Y1") (pin "2") (pinfunction "2_2") (pintype "passive"))
    )
    (net (code "20") (name "Net-(D1-PadA)") (class "Default")
      (node (ref "D1") (pin "A") (pinfunction "A_A") (pintype "passive"))
      (node (ref "R1") (pin "1") (pinfunction "1_1") (pintype "passive"))
    )
    (net (code "21") (name "Net-(D2-PadA)") (class "Default")
      (node (ref "D2") (pin "A") (pinfunction "A_A") (pintype "passive"))
      (node (ref "LED+") (pin "1") (pinfunction "1_1") (pintype "bidirectional"))
    )
    (net (code "22") (name "Net-(D2-PadC)") (class "Default")
      (node (ref "D2") (pin "C") (pinfunction "C_C") (pintype "passive"))
      (node (ref "R") (pin "1") (pinfunction "1_1") (pintype "passive"))
    )
    (net (code "23") (name "Net-(D3-PadA)") (class "Default")
      (node (ref "D3") (pin "A") (pinfunction "A_A") (pintype "passive"))
      (node (ref "LED+1") (pin "1") (pinfunction "1_1") (pintype "bidirectional"))
    )
    (net (code "24") (name "Net-(D3-PadC)") (class "Default")
      (node (ref "D3") (pin "C") (pinfunction "C_C") (pintype "passive"))
      (node (ref "R8") (pin "1") (pinfunction "1_1") (pintype "passive"))
    )
    (net (code "25") (name "Net-(D4-PadA)") (class "Default")
      (node (ref "D4") (pin "A") (pinfunction "A_A") (pintype "passive"))
      (node (ref "LED+2") (pin "1") (pinfunction "1_1") (pintype "bidirectional"))
    )
    (net (code "26") (name "Net-(D4-PadC)") (class "Default")
      (node (ref "D4") (pin "C") (pinfunction "C_C") (pintype "passive"))
      (node (ref "R9") (pin "1") (pinfunction "1_1") (pintype "passive"))
    )
    (net (code "27") (name "Net-(D5-PadA)") (class "Default")
      (node (ref "D5") (pin "A") (pinfunction "A_A") (pintype "passive"))
      (node (ref "LED+3") (pin "1") (pinfunction "1_1") (pintype "bidirectional"))
    )
    (net (code "28") (name "Net-(D5-PadC)") (class "Default")
      (node (ref "D5") (pin "C") (pinfunction "C_C") (pintype "passive"))
      (node (ref "R10") (pin "1") (pinfunction "1_1") (pintype "passive"))
    )
    (net (code "29") (name "Net-(D6-PadA)") (class "Default")
      (node (ref "D6") (pin "A") (pinfunction "A_A") (pintype "passive"))
      (node (ref "LED+4") (pin "1") (pinfunction "1_1") (pintype "bidirectional"))
    )
    (net (code "30") (name "Net-(D6-PadC)") (class "Default")
      (node (ref "D6") (pin "C") (pinfunction "C_C") (pintype "passive"))
      (node (ref "R11") (pin "1") (pinfunction "1_1") (pintype "passive"))
    )
    (net (code "31") (name "Net-(D7-PadC)") (class "Default")
      (node (ref "D7") (pin "C") (pinfunction "C_C") (pintype "passive"))
      (node (ref "R12") (pin "2") (pinfunction "2_2") (pintype "passive"))
    )
    (net (code "32") (name "Net-(D9-C)") (class "Default")
      (node (ref "D9") (pin "1") (pinfunction "C_1") (pintype "passive"))
      (node (ref "M1") (pin "P$1") (pinfunction "+_P$1") (pintype "bidirectional"))
      (node (ref "R6") (pin "1") (pinfunction "1_1") (pintype "passive"))
    )
    (net (code "33") (name "Net-(D10-BC)") (class "Default")
      (node (ref "D10") (pin "CB") (pinfunction "BC_CB") (pintype "bidirectional"))
      (node (ref "R17") (pin "2") (pinfunction "2_2") (pintype "passive"))
    )
    (net (code "34") (name "Net-(D10-GC)") (class "Default")
      (node (ref "D10") (pin "CG") (pinfunction "GC_CG") (pintype "bidirectional"))
      (node (ref "R21") (pin "2") (pinfunction "2_2") (pintype "passive"))
    )
    (net (code "35") (name "Net-(D10-RC)") (class "Default")
      (node (ref "D10") (pin "CR") (pinfunction "RC_CR") (pintype "bidirectional"))
      (node (ref "R19") (pin "2") (pinfunction "2_2") (pintype "passive"))
    )
    (net (code "36") (name "Net-(LED--Pad1)") (class "Default")
      (node (ref "LED-") (pin "1") (pinfunction "1_1") (pintype "bidirectional"))
      (node (ref "R") (pin "2") (pinfunction "2_2") (pintype "passive"))
    )
    (net (code "37") (name "Net-(LED-1-Pad1)") (class "Default")
      (node (ref "LED-1") (pin "1") (pinfunction "1_1") (pintype "bidirectional"))
      (node (ref "R8") (pin "2") (pinfunction "2_2") (pintype "passive"))
    )
    (net (code "38") (name "Net-(LED-2-Pad1)") (class "Default")
      (node (ref "LED-2") (pin "1") (pinfunction "1_1") (pintype "bidirectional"))
      (node (ref "R9") (pin "2") (pinfunction "2_2") (pintype "passive"))
    )
    (net (code "39") (name "Net-(LED-3-Pad1)") (class "Default")
      (node (ref "LED-3") (pin "1") (pinfunction "1_1") (pintype "bidirectional"))
      (node (ref "R10") (pin "2") (pinfunction "2_2") (pintype "passive"))
    )
    (net (code "40") (name "Net-(LED-4-Pad1)") (class "Default")
      (node (ref "LED-4") (pin "1") (pinfunction "1_1") (pintype "bidirectional"))
      (node (ref "R11") (pin "2") (pinfunction "2_2") (pintype "passive"))
    )
    (net (code "41") (name "Net-(U3-PB6(XTAL1{slash}TOSC1))") (class "Default")
      (node (ref "U3") (pin "7") (pinfunction "PB6(XTAL1/TOSC1)_7") (pintype "bidirectional"))
      (node (ref "Y1") (pin "1") (pinfunction "1_1") (pintype "passive"))
    )
    (net (code "42") (name "Net-(U3-PB7(XTAL2{slash}TOSC2))") (class "Default")
      (node (ref "U3") (pin "8") (pinfunction "PB7(XTAL2/TOSC2)_8") (pintype "bidirectional"))
      (node (ref "Y1") (pin "3") (pinfunction "3_3") (pintype "passive"))
    )
    (net (code "43") (name "Net-(U4-PROG)") (class "Default")
      (node (ref "R13") (pin "1") (pinfunction "1_1") (pintype "passive"))
      (node (ref "U4") (pin "5") (pinfunction "PROG_5") (pintype "input"))
    )
    (net (code "44") (name "Net-(U4-STAT)") (class "Default")
      (node (ref "R12") (pin "1") (pinfunction "1_1") (pintype "passive"))
      (node (ref "U4") (pin "1") (pinfunction "STAT_1") (pintype "output"))
    )
    (net (code "45") (name "RST") (class "Default")
      (node (ref "C4") (pin "2") (pinfunction "2_2") (pintype "passive"))
      (node (ref "PP-RST") (pin "P$1") (pinfunction "1_P$1") (pintype "bidirectional"))
      (node (ref "R2") (pin "1") (pinfunction "1_1") (pintype "passive"))
      (node (ref "S4") (pin "3") (pinfunction "2_3") (pintype "passive"))
      (node (ref "S4") (pin "4") (pinfunction "2_4") (pintype "passive"))
      (node (ref "U3") (pin "29") (pinfunction "PC6(/RESET)_29") (pintype "bidirectional"))
    )
    (net (code "46") (name "RXI") (class "Default")
      (node (ref "JP2") (pin "3") (pinfunction "TXO_3") (pintype "passive"))
      (node (ref "TP-RX") (pin "P$1") (pinfunction "1_P$1") (pintype "bidirectional"))
      (node (ref "U3") (pin "30") (pinfunction "PD0(RXD)_30") (pintype "bidirectional"))
    )
    (net (code "47") (name "SINK1") (class "Default")
      (node (ref "S2") (pin "4") (pinfunction "6_4") (pintype "bidirectional"))
    )
    (net (code "48") (name "SINK2") (class "Default")
      (node (ref "S2") (pin "1") (pinfunction "3_1") (pintype "bidirectional"))
    )
    (net (code "49") (name "TXO") (class "Default")
      (node (ref "JP2") (pin "2") (pinfunction "RXI_2") (pintype "passive"))
      (node (ref "TP-TX") (pin "P$1") (pinfunction "1_P$1") (pintype "bidirectional"))
      (node (ref "U3") (pin "31") (pinfunction "PD1(TXD)_31") (pintype "bidirectional"))
    )
    (net (code "50") (name "VBATT") (class "Default")
      (node (ref "C10") (pin "1") (pinfunction "1_1") (pintype "passive"))
      (node (ref "D8") (pin "A") (pinfunction "A_A") (pintype "passive"))
      (node (ref "JP1") (pin "2") (pinfunction "2_2") (pintype "passive"))
      (node (ref "S1") (pin "1") (pinfunction "3_1") (pintype "bidirectional"))
      (node (ref "S1") (pin "4") (pinfunction "6_4") (pintype "bidirectional"))
      (node (ref "TP2") (pin "P$1") (pinfunction "1_P$1") (pintype "bidirectional"))
      (node (ref "U4") (pin "3") (pinfunction "VBAT_3") (pintype "power_in"))
    )
    (net (code "51") (name "VCC") (class "Default")
      (node (ref "C1") (pin "1") (pinfunction "1_1") (pintype "passive"))
      (node (ref "C2") (pin "A") (pinfunction "+_A") (pintype "passive"))
      (node (ref "C3") (pin "1") (pinfunction "1_1") (pintype "passive"))
      (node (ref "C5") (pin "1") (pinfunction "1_1") (pintype "passive"))
      (node (ref "LIGHT+") (pin "1") (pinfunction "1_1") (pintype "bidirectional"))
      (node (ref "R2") (pin "2") (pinfunction "2_2") (pintype "passive"))
      (node (ref "S1") (pin "2") (pinfunction "2_2") (pintype "bidirectional"))
      (node (ref "S1") (pin "5") (pinfunction "5_5") (pintype "bidirectional"))
      (node (ref "TEMP+") (pin "1") (pinfunction "1_1") (pintype "bidirectional"))
      (node (ref "U$2") (pin "P$2") (pinfunction "P$2_P$2") (pintype "bidirectional"))
      (node (ref "U$33") (pin "P$2") (pinfunction "P$2_P$2") (pintype "bidirectional"))
      (node (ref "U$45") (pin "1") (pinfunction "1_1") (pintype "bidirectional"))
      (node (ref "U$8") (pin "P$4") (pinfunction "P$4_P$4") (pintype "bidirectional"))
      (node (ref "U2") (pin "1") (pinfunction "VCC_1") (pintype "bidirectional"))
      (node (ref "U3") (pin "18") (pinfunction "AVCC_18") (pintype "bidirectional"))
      (node (ref "U3") (pin "20") (pinfunction "AREF_20") (pintype "bidirectional"))
      (node (ref "U3") (pin "4") (pinfunction "VCC_4") (pintype "bidirectional"))
      (node (ref "U3") (pin "6") (pinfunction "VCC_6") (pintype "bidirectional"))
      (node (ref "U6") (pin "C") (pinfunction "C1_C") (pintype "passive"))
    )
    (net (code "52") (name "unconnected-(U$3-PadP$2)") (class "Default")
      (node (ref "U$3") (pin "P$2") (pinfunction "P$2_P$2") (pintype "bidirectional"))
    )
    (net (code "53") (name "unconnected-(U$6-PadP$2)") (class "Default")
      (node (ref "U$6") (pin "P$2") (pinfunction "P$2_P$2") (pintype "bidirectional"))
    )
    (net (code "54") (name "unconnected-(U$7-PadP$2)") (class "Default")
      (node (ref "U$7") (pin "P$2") (pinfunction "P$2_P$2") (pintype "bidirectional"))
    )
    (net (code "55") (name "unconnected-(U$8-PadP$6)") (class "Default")
      (node (ref "U$8") (pin "P$6") (pinfunction "P$6_P$6") (pintype "bidirectional"))
    )
    (net (code "56") (name "unconnected-(U$20-PadP$1)") (class "Default")
      (node (ref "U$20") (pin "P$1") (pinfunction "P$1_P$1") (pintype "bidirectional"))
    )
    (net (code "57") (name "unconnected-(U$47-PadP$2)") (class "Default")
      (node (ref "U$47") (pin "P$2") (pinfunction "P$2_P$2") (pintype "bidirectional"))
    )
    (net (code "58") (name "unconnected-(U$48-PadP$2)") (class "Default")
      (node (ref "U$48") (pin "P$2") (pinfunction "P$2_P$2") (pintype "bidirectional"))
    )
    (net (code "59") (name "unconnected-(U3-ADC7-Pad22)") (class "Default")
      (node (ref "U3") (pin "22") (pinfunction "ADC7_22") (pintype "bidirectional"))
    )
    (net (code "60") (name "unconnected-(U3-PB0(ICP)-Pad12)") (class "Default")
      (node (ref "U3") (pin "12") (pinfunction "PB0(ICP)_12") (pintype "bidirectional"))
    )
    (net (code "61") (name "unconnected-(U3-PC0(ADC0)-Pad23)") (class "Default")
      (node (ref "U3") (pin "23") (pinfunction "PC0(ADC0)_23") (pintype "bidirectional"))
    )
    (net (code "62") (name "unconnected-(U3-PD4(XCK{slash}T0)-Pad2)") (class "Default")
      (node (ref "U3") (pin "2") (pinfunction "PD4(XCK/T0)_2") (pintype "bidirectional"))
    )
  )
)
